# Sheet2.net
KiCad netlist of a schematic drawn in Altium Designer
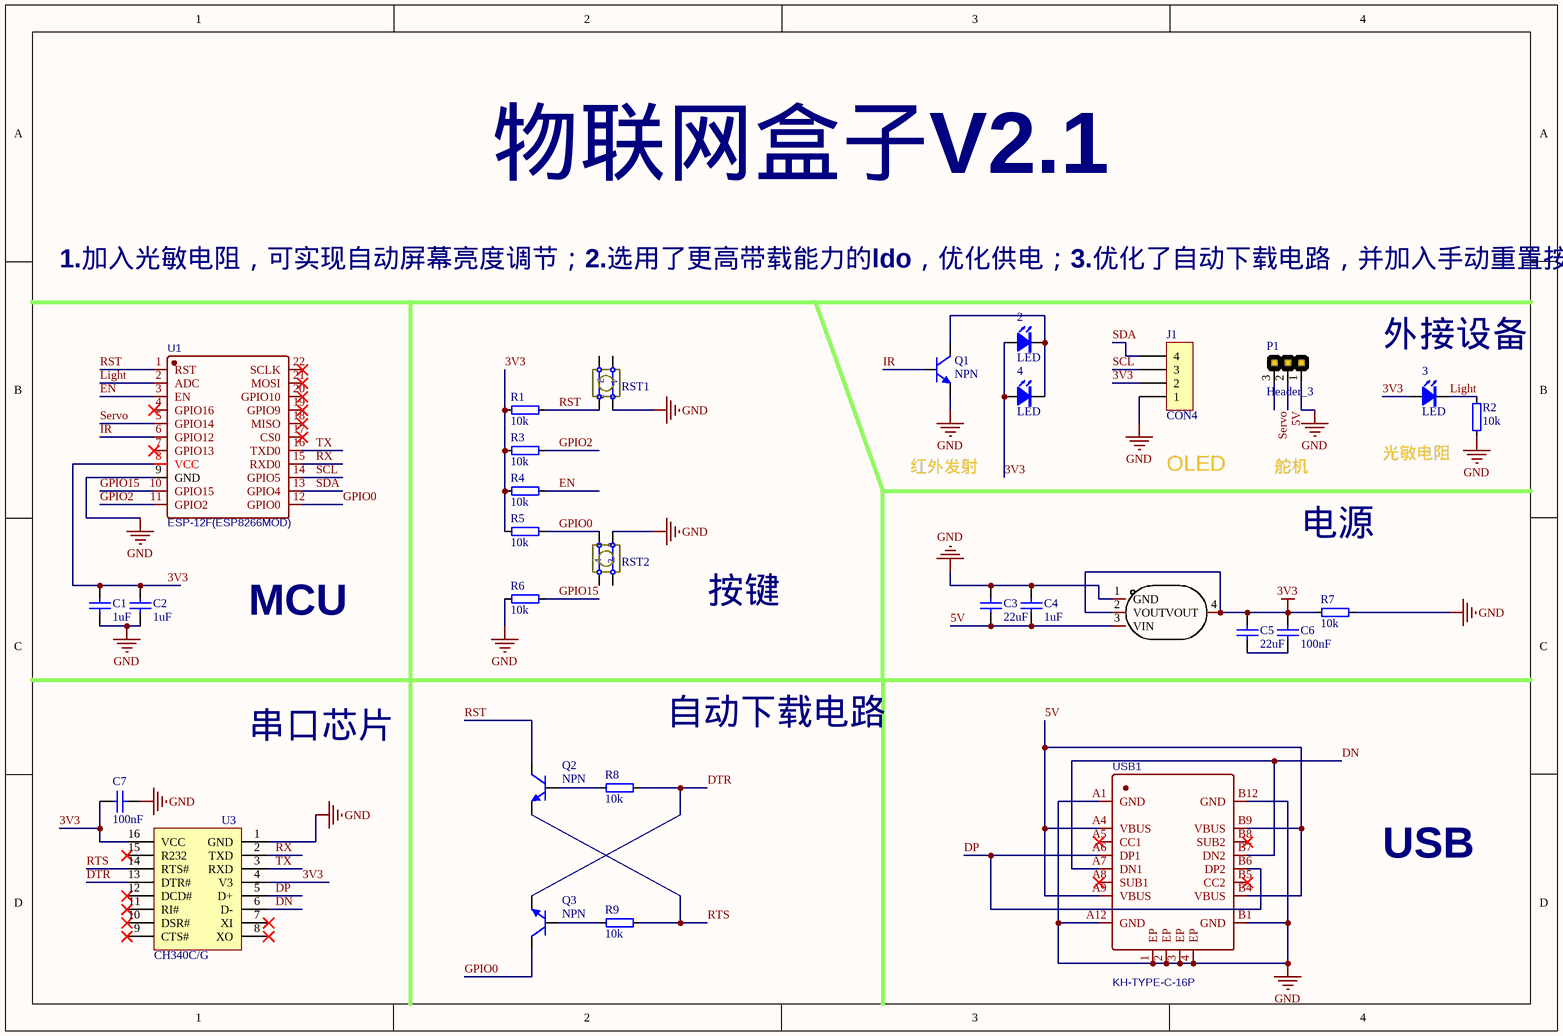
[diagram p0: Sheet2.SchDoc]

(export (version "E")
  (design (tool "Eeschema 10.0.6"))
  (components
    (comp (ref "2") (value "LED") (footprint "D1") (libsource (lib "模拟器件") (part "LED")))
    (comp (ref "3") (value "LED") (footprint "D1") (libsource (lib "模拟器件") (part "LED")))
    (comp (ref "4") (value "LED") (footprint "D1") (libsource (lib "模拟器件") (part "LED")))
    (comp (ref "C1")
      (value "1uF")
      (footprint "0603S")
      (description "电容0805")
      (libsource (lib "常用贴片器件库") (part "电容0805"))
    )
    (comp (ref "C2")
      (value "1uF")
      (footprint "0603S")
      (description "电容0805")
      (libsource (lib "常用贴片器件库") (part "电容0805"))
    )
    (comp (ref "C3")
      (value "22uF")
      (footprint "0603S")
      (description "电容0805")
      (libsource (lib "常用贴片器件库") (part "电容0805"))
    )
    (comp (ref "C4")
      (value "1uF")
      (footprint "0603S")
      (description "电容0805")
      (libsource (lib "常用贴片器件库") (part "电容0805"))
    )
    (comp (ref "C5")
      (value "22uF")
      (footprint "0603S")
      (description "电容0805")
      (libsource (lib "常用贴片器件库") (part "电容0805"))
    )
    (comp (ref "C6")
      (value "100nF")
      (footprint "0603S")
      (description "电容0805")
      (libsource (lib "常用贴片器件库") (part "电容0805"))
    )
    (comp (ref "C7")
      (value "100nF")
      (footprint "0603S")
      (description "电容0805")
      (libsource (lib "常用贴片器件库") (part "电容0805"))
    )
    (comp (ref "J1")
      (value "CON4")
      (footprint "HDR1X4")
      (description "Connector")
      (libsource (lib "插件") (part "CON4"))
    )
    (comp (ref "P1")
      (value "Header_3")
      (footprint "Header_3")
      (description "插针")
      (libsource (lib "常用直插器件库") (part "Header_3"))
    )
    (comp (ref "Q1")
      (value "NPN")
      (footprint "SOT-23")
      (description "triode")
      (libsource (lib "模拟器件") (part "NPN"))
    )
    (comp (ref "Q2")
      (value "NPN")
      (footprint "SOT-23")
      (description "triode")
      (libsource (lib "模拟器件") (part "NPN"))
    )
    (comp (ref "Q3")
      (value "NPN")
      (footprint "SOT-23")
      (description "triode")
      (libsource (lib "模拟器件") (part "NPN"))
    )
    (comp (ref "R1") (value "10k") (footprint "0603S") (libsource (lib "电阻") (part "RES")))
    (comp (ref "R2") (value "10k") (footprint "0603S") (libsource (lib "电阻") (part "RES")))
    (comp (ref "R3") (value "10k") (footprint "0603S") (libsource (lib "电阻") (part "RES")))
    (comp (ref "R4") (value "10k") (footprint "0603S") (libsource (lib "电阻") (part "RES")))
    (comp (ref "R5") (value "10k") (footprint "0603S") (libsource (lib "电阻") (part "RES")))
    (comp (ref "R6") (value "10k") (footprint "0603S") (libsource (lib "电阻") (part "RES")))
    (comp (ref "R7") (value "10k") (footprint "0603S") (libsource (lib "电阻") (part "RES")))
    (comp (ref "R8") (value "10k") (footprint "0603S") (libsource (lib "电阻") (part "RES")))
    (comp (ref "R9") (value "10k") (footprint "0603S") (libsource (lib "电阻") (part "RES")))
    (comp (ref "RST1")
      (value "SW-PB")
      (footprint "SW-SMD_TSA365G00-250")
      (description "微动开关，轻触按键")
      (libsource (lib "原理图库") (part "SW-PB"))
    )
    (comp (ref "RST2")
      (value "SW-PB")
      (footprint "SW-SMD_TSA365G00-250")
      (description "微动开关，轻触按键")
      (libsource (lib "原理图库") (part "SW-PB"))
    )
    (comp (ref "U1")
      (value "ESP-12F(ESP8266MOD)")
      (footprint "WIFIM-SMD_ESP-12F-ESP8266MOD")
      (fields (field (name "BOM_SUPPLIER PART") "C82891"))
      (libsource (lib "Integrated_Library1") (part "ESP-12F(ESP8266MOD)"))
    )
    (comp (ref "U2")
      (value "AMS1117-3.3")
      (footprint "SOT-223-3_L6.7-W3.7-P2.30-LS7.0-BR")
      (fields (field (name "MANUFACTURER") "JSMSEMI(杰盛微)"))
      (libsource (lib "Integrated_Library1") (part "AMS1117-3.3"))
    )
    (comp (ref "U3")
      (value "CH340C/G")
      (footprint "SOP16")
      (description "USB转COM口")
      (libsource (lib "原理图库") (part "CH340G"))
    )
    (comp (ref "USB1")
      (value "KH-TYPE-C-16P")
      (footprint "USB-C-SMD_KH-TYPE-C-16P")
      (fields (field (name "BOM_SUPPLIER PART") "C709357") (field (name "CONTRIBUTOR") "LCSC"))
      (libsource (lib "Integrated_Library1") (part "KH-TYPE-C-16P"))
    )
  )
  (nets
    (net (code "1") (name "/5V") (class "Default")
      (node (ref "C3") (pin "2") (pinfunction "2_2") (pintype "passive"))
      (node (ref "C4") (pin "2") (pinfunction "2_2") (pintype "passive"))
      (node (ref "P1") (pin "2") (pinfunction "2_2") (pintype "passive"))
      (node (ref "U2") (pin "3") (pinfunction "VIN_3") (pintype "passive"))
      (node (ref "USB1") (pin "A4") (pinfunction "VBUS_A4") (pintype "passive"))
      (node (ref "USB1") (pin "A9") (pinfunction "VBUS_A9") (pintype "passive"))
      (node (ref "USB1") (pin "B4") (pinfunction "VBUS_B4") (pintype "passive"))
      (node (ref "USB1") (pin "B9") (pinfunction "VBUS_B9") (pintype "passive"))
    )
    (net (code "2") (name "/DN") (class "Default")
      (node (ref "U3") (pin "6") (pinfunction "D-_6") (pintype "passive"))
      (node (ref "USB1") (pin "A7") (pinfunction "DN1_A7") (pintype "passive"))
      (node (ref "USB1") (pin "B7") (pinfunction "DN2_B7") (pintype "passive"))
    )
    (net (code "3") (name "/DP") (class "Default")
      (node (ref "U3") (pin "5") (pinfunction "D+_5") (pintype "passive"))
      (node (ref "USB1") (pin "A6") (pinfunction "DP1_A6") (pintype "passive"))
      (node (ref "USB1") (pin "B6") (pinfunction "DP2_B6") (pintype "passive"))
    )
    (net (code "4") (name "/DTR") (class "Default")
      (node (ref "Q3") (pin "1") (pinfunction "E_1") (pintype "passive"))
      (node (ref "R8") (pin "2") (pinfunction "2_2") (pintype "passive"))
      (node (ref "U3") (pin "13") (pinfunction "DTR#_13") (pintype "passive"))
    )
    (net (code "5") (name "/EN") (class "Default")
      (node (ref "R4") (pin "2") (pinfunction "2_2") (pintype "passive"))
      (node (ref "U1") (pin "3") (pinfunction "EN_3") (pintype "passive"))
    )
    (net (code "6") (name "/GPIO0") (class "Default")
      (node (ref "Q3") (pin "3") (pinfunction "C_3") (pintype "passive"))
      (node (ref "R5") (pin "2") (pinfunction "2_2") (pintype "passive"))
      (node (ref "RST2") (pin "1") (pinfunction "1_1") (pintype "passive"))
      (node (ref "U1") (pin "12") (pinfunction "GPIO0_12") (pintype "passive"))
    )
    (net (code "7") (name "/GPIO2") (class "Default")
      (node (ref "R3") (pin "2") (pinfunction "2_2") (pintype "passive"))
      (node (ref "U1") (pin "11") (pinfunction "GPIO2_11") (pintype "passive"))
    )
    (net (code "8") (name "/GPIO15") (class "Default")
      (node (ref "R6") (pin "2") (pinfunction "2_2") (pintype "passive"))
      (node (ref "U1") (pin "10") (pinfunction "GPIO15_10") (pintype "passive"))
    )
    (net (code "9") (name "/IR") (class "Default")
      (node (ref "Q1") (pin "2") (pinfunction "B_2") (pintype "passive"))
      (node (ref "U1") (pin "6") (pinfunction "GPIO12_6") (pintype "passive"))
    )
    (net (code "10") (name "/Light") (class "Default")
      (node (ref "3") (pin "2") (pinfunction "K_2") (pintype "passive"))
      (node (ref "R2") (pin "2") (pinfunction "2_2") (pintype "passive"))
      (node (ref "U1") (pin "2") (pinfunction "ADC_2") (pintype "passive"))
    )
    (net (code "11") (name "/RST") (class "Default")
      (node (ref "Q2") (pin "3") (pinfunction "C_3") (pintype "passive"))
      (node (ref "R1") (pin "2") (pinfunction "2_2") (pintype "passive"))
      (node (ref "RST1") (pin "2") (pinfunction "2_2") (pintype "passive"))
      (node (ref "U1") (pin "1") (pinfunction "RST_1") (pintype "passive"))
    )
    (net (code "12") (name "/RTS") (class "Default")
      (node (ref "Q2") (pin "1") (pinfunction "E_1") (pintype "passive"))
      (node (ref "R9") (pin "2") (pinfunction "2_2") (pintype "passive"))
      (node (ref "U3") (pin "14") (pinfunction "RTS#_14") (pintype "passive"))
    )
    (net (code "13") (name "/RX") (class "Default")
      (node (ref "U1") (pin "15") (pinfunction "RXD0_15") (pintype "passive"))
      (node (ref "U3") (pin "2") (pinfunction "TXD_2") (pintype "passive"))
    )
    (net (code "14") (name "/SCL") (class "Default")
      (node (ref "J1") (pin "3") (pinfunction "3_3") (pintype "passive"))
      (node (ref "U1") (pin "14") (pinfunction "GPIO5_14") (pintype "passive"))
    )
    (net (code "15") (name "/SDA") (class "Default")
      (node (ref "J1") (pin "4") (pinfunction "4_4") (pintype "passive"))
      (node (ref "U1") (pin "13") (pinfunction "GPIO4_13") (pintype "passive"))
    )
    (net (code "16") (name "/Servo") (class "Default")
      (node (ref "P1") (pin "3") (pinfunction "3_3") (pintype "passive"))
      (node (ref "U1") (pin "5") (pinfunction "GPIO14_5") (pintype "passive"))
    )
    (net (code "17") (name "/TX") (class "Default")
      (node (ref "U1") (pin "16") (pinfunction "TXD0_16") (pintype "passive"))
      (node (ref "U3") (pin "3") (pinfunction "RXD_3") (pintype "passive"))
    )
    (net (code "18") (name "3V3") (class "Default")
      (node (ref "2") (pin "1") (pinfunction "A_1") (pintype "passive"))
      (node (ref "3") (pin "1") (pinfunction "A_1") (pintype "passive"))
      (node (ref "4") (pin "1") (pinfunction "A_1") (pintype "passive"))
      (node (ref "C1") (pin "1") (pinfunction "1_1") (pintype "passive"))
      (node (ref "C2") (pin "1") (pinfunction "1_1") (pintype "passive"))
      (node (ref "C5") (pin "1") (pinfunction "1_1") (pintype "passive"))
      (node (ref "C6") (pin "1") (pinfunction "1_1") (pintype "passive"))
      (node (ref "C7") (pin "2") (pinfunction "2_2") (pintype "passive"))
      (node (ref "J1") (pin "2") (pinfunction "2_2") (pintype "power_in"))
      (node (ref "R1") (pin "1") (pinfunction "1_1") (pintype "passive"))
      (node (ref "R3") (pin "1") (pinfunction "1_1") (pintype "passive"))
      (node (ref "R4") (pin "1") (pinfunction "1_1") (pintype "passive"))
      (node (ref "R5") (pin "1") (pinfunction "1_1") (pintype "passive"))
      (node (ref "R7") (pin "1") (pinfunction "1_1") (pintype "passive"))
      (node (ref "U1") (pin "8") (pinfunction "VCC_8") (pintype "passive"))
      (node (ref "U2") (pin "2") (pinfunction "VOUT_2") (pintype "passive"))
      (node (ref "U2") (pin "4") (pinfunction "VOUT_4") (pintype "passive"))
      (node (ref "U3") (pin "16") (pinfunction "VCC_16") (pintype "passive"))
      (node (ref "U3") (pin "4") (pinfunction "V3_4") (pintype "passive"))
    )
    (net (code "19") (name "GND") (class "Default")
      (node (ref "C1") (pin "2") (pinfunction "2_2") (pintype "passive"))
      (node (ref "C2") (pin "2") (pinfunction "2_2") (pintype "passive"))
      (node (ref "C3") (pin "1") (pinfunction "1_1") (pintype "passive"))
      (node (ref "C4") (pin "1") (pinfunction "1_1") (pintype "passive"))
      (node (ref "C7") (pin "1") (pinfunction "1_1") (pintype "passive"))
      (node (ref "J1") (pin "1") (pinfunction "1_1") (pintype "power_in"))
      (node (ref "P1") (pin "1") (pinfunction "1_1") (pintype "passive"))
      (node (ref "Q1") (pin "1") (pinfunction "E_1") (pintype "passive"))
      (node (ref "R2") (pin "1") (pinfunction "1_1") (pintype "passive"))
      (node (ref "R6") (pin "1") (pinfunction "1_1") (pintype "passive"))
      (node (ref "R7") (pin "2") (pinfunction "2_2") (pintype "passive"))
      (node (ref "RST1") (pin "1") (pinfunction "1_1") (pintype "passive"))
      (node (ref "RST2") (pin "2") (pinfunction "2_2") (pintype "passive"))
      (node (ref "U1") (pin "9") (pinfunction "GND_9") (pintype "passive"))
      (node (ref "U2") (pin "1") (pinfunction "GND_1") (pintype "passive"))
      (node (ref "U3") (pin "1") (pinfunction "GND_1") (pintype "passive"))
      (node (ref "USB1") (pin "1") (pinfunction "EP_1") (pintype "passive"))
      (node (ref "USB1") (pin "2") (pinfunction "EP_2") (pintype "passive"))
      (node (ref "USB1") (pin "3") (pinfunction "EP_3") (pintype "passive"))
      (node (ref "USB1") (pin "4") (pinfunction "EP_4") (pintype "passive"))
      (node (ref "USB1") (pin "A1") (pinfunction "GND_A1") (pintype "passive"))
      (node (ref "USB1") (pin "A12") (pinfunction "GND_A12") (pintype "passive"))
      (node (ref "USB1") (pin "B1") (pinfunction "GND_B1") (pintype "passive"))
      (node (ref "USB1") (pin "B12") (pinfunction "GND_B12") (pintype "passive"))
    )
    (net (code "20") (name "Net-(2-K)") (class "Default")
      (node (ref "2") (pin "2") (pinfunction "K_2") (pintype "passive"))
      (node (ref "4") (pin "2") (pinfunction "K_2") (pintype "passive"))
      (node (ref "Q1") (pin "3") (pinfunction "C_3") (pintype "passive"))
    )
    (net (code "21") (name "Net-(C5-Pad2)") (class "Default")
      (node (ref "C5") (pin "2") (pinfunction "2_2") (pintype "passive"))
      (node (ref "C6") (pin "2") (pinfunction "2_2") (pintype "passive"))
    )
    (net (code "22") (name "Net-(Q2-B)") (class "Default")
      (node (ref "Q2") (pin "2") (pinfunction "B_2") (pintype "passive"))
      (node (ref "R8") (pin "1") (pinfunction "1_1") (pintype "passive"))
    )
    (net (code "23") (name "Net-(Q3-B)") (class "Default")
      (node (ref "Q3") (pin "2") (pinfunction "B_2") (pintype "passive"))
      (node (ref "R9") (pin "1") (pinfunction "1_1") (pintype "passive"))
    )
    (net (code "24") (name "unconnected-(RST1-Pad3)") (class "Default")
      (node (ref "RST1") (pin "3") (pinfunction "3_3") (pintype "passive"))
    )
    (net (code "25") (name "unconnected-(RST1-Pad4)") (class "Default")
      (node (ref "RST1") (pin "4") (pinfunction "4_4") (pintype "passive"))
    )
    (net (code "26") (name "unconnected-(RST2-Pad3)") (class "Default")
      (node (ref "RST2") (pin "3") (pinfunction "3_3") (pintype "passive"))
    )
    (net (code "27") (name "unconnected-(RST2-Pad4)") (class "Default")
      (node (ref "RST2") (pin "4") (pinfunction "4_4") (pintype "passive"))
    )
    (net (code "28") (name "unconnected-(U1-CS0-Pad17)") (class "Default")
      (node (ref "U1") (pin "17") (pinfunction "CS0_17") (pintype "passive+no_connect"))
    )
    (net (code "29") (name "unconnected-(U1-GPIO9-Pad19)") (class "Default")
      (node (ref "U1") (pin "19") (pinfunction "GPIO9_19") (pintype "passive+no_connect"))
    )
    (net (code "30") (name "unconnected-(U1-GPIO10-Pad20)") (class "Default")
      (node (ref "U1") (pin "20") (pinfunction "GPIO10_20") (pintype "passive+no_connect"))
    )
    (net (code "31") (name "unconnected-(U1-GPIO13-Pad7)") (class "Default")
      (node (ref "U1") (pin "7") (pinfunction "GPIO13_7") (pintype "passive+no_connect"))
    )
    (net (code "32") (name "unconnected-(U1-GPIO16-Pad4)") (class "Default")
      (node (ref "U1") (pin "4") (pinfunction "GPIO16_4") (pintype "passive+no_connect"))
    )
    (net (code "33") (name "unconnected-(U1-MISO-Pad18)") (class "Default")
      (node (ref "U1") (pin "18") (pinfunction "MISO_18") (pintype "passive+no_connect"))
    )
    (net (code "34") (name "unconnected-(U1-MOSI-Pad21)") (class "Default")
      (node (ref "U1") (pin "21") (pinfunction "MOSI_21") (pintype "passive+no_connect"))
    )
    (net (code "35") (name "unconnected-(U1-SCLK-Pad22)") (class "Default")
      (node (ref "U1") (pin "22") (pinfunction "SCLK_22") (pintype "passive+no_connect"))
    )
    (net (code "36") (name "unconnected-(U3-CTS#-Pad9)") (class "Default")
      (node (ref "U3") (pin "9") (pinfunction "CTS#_9") (pintype "passive+no_connect"))
    )
    (net (code "37") (name "unconnected-(U3-DCD#-Pad12)") (class "Default")
      (node (ref "U3") (pin "12") (pinfunction "DCD#_12") (pintype "passive+no_connect"))
    )
    (net (code "38") (name "unconnected-(U3-DSR#-Pad10)") (class "Default")
      (node (ref "U3") (pin "10") (pinfunction "DSR#_10") (pintype "passive+no_connect"))
    )
    (net (code "39") (name "unconnected-(U3-R232-Pad15)") (class "Default")
      (node (ref "U3") (pin "15") (pinfunction "R232_15") (pintype "passive+no_connect"))
    )
    (net (code "40") (name "unconnected-(U3-RI#-Pad11)") (class "Default")
      (node (ref "U3") (pin "11") (pinfunction "RI#_11") (pintype "passive+no_connect"))
    )
    (net (code "41") (name "unconnected-(U3-XI-Pad7)") (class "Default")
      (node (ref "U3") (pin "7") (pinfunction "XI_7") (pintype "passive+no_connect"))
    )
    (net (code "42") (name "unconnected-(U3-XO-Pad8)") (class "Default")
      (node (ref "U3") (pin "8") (pinfunction "XO_8") (pintype "passive+no_connect"))
    )
    (net (code "43") (name "unconnected-(USB1-CC1-PadA5)") (class "Default")
      (node (ref "USB1") (pin "A5") (pinfunction "CC1_A5") (pintype "passive+no_connect"))
    )
    (net (code "44") (name "unconnected-(USB1-CC2-PadB5)") (class "Default")
      (node (ref "USB1") (pin "B5") (pinfunction "CC2_B5") (pintype "passive+no_connect"))
    )
    (net (code "45") (name "unconnected-(USB1-SUB1-PadA8)") (class "Default")
      (node (ref "USB1") (pin "A8") (pinfunction "SUB1_A8") (pintype "passive+no_connect"))
    )
    (net (code "46") (name "unconnected-(USB1-SUB2-PadB8)") (class "Default")
      (node (ref "USB1") (pin "B8") (pinfunction "SUB2_B8") (pintype "passive+no_connect"))
    )
  )
)
